# syncbox.net
KiCad netlist of a schematic drawn in EAGLE
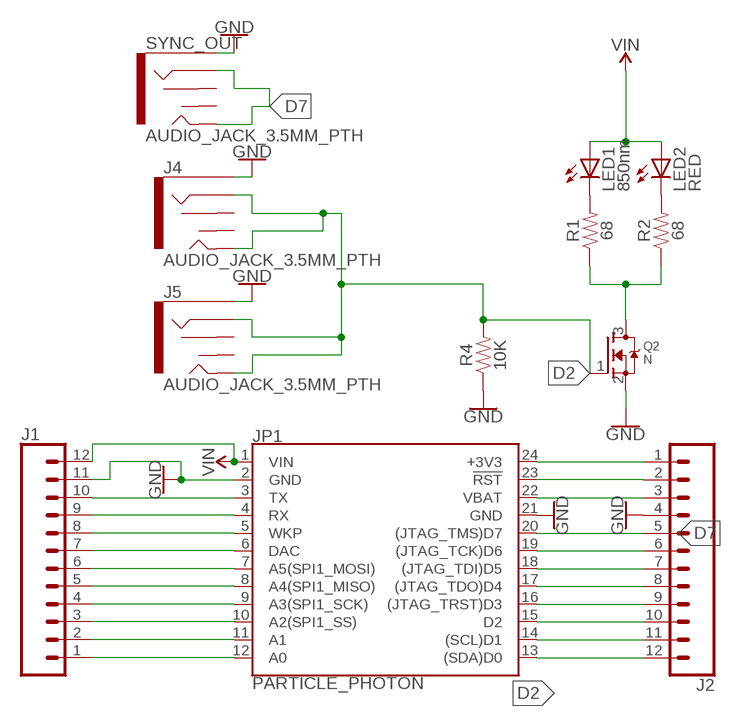
[diagram p0: schematic, sheet 1]

(export (version "E")
  (design (tool "Eeschema 10.0.6"))
  (components
    (comp (ref "J1")
      (value "CONN_12")
      (footprint "eagle-import:1X12")
      (libsource (lib "eagle-import") (part "CONN_12"))
    )
    (comp (ref "J2")
      (value "CONN_12")
      (footprint "eagle-import:1X12")
      (libsource (lib "eagle-import") (part "CONN_12"))
    )
    (comp (ref "J4")
      (value "AUDIO_JACK_3.5MM_PTH")
      (footprint "eagle-import:AUDIO-JACK")
      (libsource (lib "eagle-import") (part "AUDIO_JACK_3.5MM_PTH"))
    )
    (comp (ref "J5")
      (value "AUDIO_JACK_3.5MM_PTH")
      (footprint "eagle-import:AUDIO-JACK")
      (libsource (lib "eagle-import") (part "AUDIO_JACK_3.5MM_PTH"))
    )
    (comp (ref "JP1")
      (value "PARTICLE_PHOTON")
      (footprint "eagle-import:PARTICLE_PHOTON")
      (libsource (lib "eagle-import") (part "PARTICLE_PHOTON"))
    )
    (comp (ref "LED1")
      (value "850nm")
      (footprint "eagle-import:LED5MM")
      (libsource (lib "eagle-import") (part "LED5MM"))
    )
    (comp (ref "LED2")
      (value "RED")
      (footprint "eagle-import:LED5MM")
      (libsource (lib "eagle-import") (part "LED5MM"))
    )
    (comp (ref "Q2")
      (value "N")
      (footprint "eagle-import:SOT23-W")
      (libsource (lib "eagle-import") (part "MOSFET-NWAVE"))
    )
    (comp (ref "R1")
      (value "68")
      (footprint "eagle-import:AXIAL-0.3")
      (libsource (lib "eagle-import") (part "RESISTORAXIAL-0.3"))
    )
    (comp (ref "R2")
      (value "68")
      (footprint "eagle-import:AXIAL-0.3")
      (libsource (lib "eagle-import") (part "RESISTORAXIAL-0.3"))
    )
    (comp (ref "R4")
      (value "10K")
      (footprint "eagle-import:AXIAL-0.3")
      (libsource (lib "eagle-import") (part "RESISTORAXIAL-0.3"))
    )
    (comp (ref "SYNC_OUT")
      (value "AUDIO_JACK_3.5MM_PTH")
      (footprint "eagle-import:AUDIO-JACK")
      (libsource (lib "eagle-import") (part "AUDIO_JACK_3.5MM_PTH"))
    )
  )
  (nets
    (net (code "1") (name "D2") (class "Default")
      (node (ref "J2") (pin "10") (pinfunction "10_10") (pintype "passive"))
      (node (ref "J4") (pin "RING") (pinfunction "RING_RING") (pintype "bidirectional"))
      (node (ref "J4") (pin "TIP") (pinfunction "TIP_TIP") (pintype "bidirectional"))
      (node (ref "J5") (pin "RING") (pinfunction "RING_RING") (pintype "bidirectional"))
      (node (ref "J5") (pin "TIP") (pinfunction "TIP_TIP") (pintype "bidirectional"))
      (node (ref "JP1") (pin "15") (pinfunction "D2_15") (pintype "bidirectional"))
      (node (ref "Q2") (pin "1") (pinfunction "G_1") (pintype "bidirectional"))
      (node (ref "R4") (pin "P$2") (pinfunction "2_P$2") (pintype "passive"))
    )
    (net (code "2") (name "D7") (class "Default")
      (node (ref "J2") (pin "5") (pinfunction "5_5") (pintype "passive"))
      (node (ref "JP1") (pin "20") (pinfunction "(JTAG_TMS)D7_20") (pintype "bidirectional"))
      (node (ref "SYNC_OUT") (pin "RING") (pinfunction "RING_RING") (pintype "bidirectional"))
      (node (ref "SYNC_OUT") (pin "TIP") (pinfunction "TIP_TIP") (pintype "bidirectional"))
    )
    (net (code "3") (name "GND") (class "Default")
      (node (ref "J1") (pin "11") (pinfunction "11_11") (pintype "passive"))
      (node (ref "J2") (pin "4") (pinfunction "4_4") (pintype "passive"))
      (node (ref "J4") (pin "SLEEVE") (pinfunction "SLEEVE_SLEEVE") (pintype "bidirectional"))
      (node (ref "J5") (pin "SLEEVE") (pinfunction "SLEEVE_SLEEVE") (pintype "bidirectional"))
      (node (ref "JP1") (pin "2") (pinfunction "GND_2") (pintype "power_in"))
      (node (ref "JP1") (pin "21") (pinfunction "GND_21") (pintype "power_in"))
      (node (ref "Q2") (pin "2") (pinfunction "S_2") (pintype "bidirectional"))
      (node (ref "R4") (pin "P$1") (pinfunction "1_P$1") (pintype "passive"))
      (node (ref "SYNC_OUT") (pin "SLEEVE") (pinfunction "SLEEVE_SLEEVE") (pintype "bidirectional"))
    )
    (net (code "4") (name "Net-(JP1-(JTAG_TCK)D6)") (class "Default")
      (node (ref "J2") (pin "6") (pinfunction "6_6") (pintype "passive"))
      (node (ref "JP1") (pin "19") (pinfunction "(JTAG_TCK)D6_19") (pintype "bidirectional"))
    )
    (net (code "5") (name "Net-(JP1-(JTAG_TDI)D5)") (class "Default")
      (node (ref "J2") (pin "7") (pinfunction "7_7") (pintype "passive"))
      (node (ref "JP1") (pin "18") (pinfunction "(JTAG_TDI)D5_18") (pintype "bidirectional"))
    )
    (net (code "6") (name "Net-(JP1-(JTAG_TDO)D4)") (class "Default")
      (node (ref "J2") (pin "8") (pinfunction "8_8") (pintype "passive"))
      (node (ref "JP1") (pin "17") (pinfunction "(JTAG_TDO)D4_17") (pintype "bidirectional"))
    )
    (net (code "7") (name "Net-(JP1-(JTAG_TRST)D3)") (class "Default")
      (node (ref "J2") (pin "9") (pinfunction "9_9") (pintype "passive"))
      (node (ref "JP1") (pin "16") (pinfunction "(JTAG_TRST)D3_16") (pintype "bidirectional"))
    )
    (net (code "8") (name "Net-(JP1-(SCL)D1)") (class "Default")
      (node (ref "J2") (pin "11") (pinfunction "11_11") (pintype "passive"))
      (node (ref "JP1") (pin "14") (pinfunction "(SCL)D1_14") (pintype "bidirectional"))
    )
    (net (code "9") (name "Net-(JP1-(SDA)D0)") (class "Default")
      (node (ref "J2") (pin "12") (pinfunction "12_12") (pintype "passive"))
      (node (ref "JP1") (pin "13") (pinfunction "(SDA)D0_13") (pintype "bidirectional"))
    )
    (net (code "10") (name "Net-(JP1-+3V3)") (class "Default")
      (node (ref "J2") (pin "1") (pinfunction "1_1") (pintype "passive"))
      (node (ref "JP1") (pin "24") (pinfunction "+3V3_24") (pintype "power_in"))
    )
    (net (code "11") (name "Net-(JP1-A0)") (class "Default")
      (node (ref "J1") (pin "1") (pinfunction "1_1") (pintype "passive"))
      (node (ref "JP1") (pin "12") (pinfunction "A0_12") (pintype "bidirectional"))
    )
    (net (code "12") (name "Net-(JP1-A1)") (class "Default")
      (node (ref "J1") (pin "2") (pinfunction "2_2") (pintype "passive"))
      (node (ref "JP1") (pin "11") (pinfunction "A1_11") (pintype "bidirectional"))
    )
    (net (code "13") (name "Net-(JP1-A2(SPI1_SS))") (class "Default")
      (node (ref "J1") (pin "3") (pinfunction "3_3") (pintype "passive"))
      (node (ref "JP1") (pin "10") (pinfunction "A2(SPI1_SS)_10") (pintype "bidirectional"))
    )
    (net (code "14") (name "Net-(JP1-A3(SPI1_SCK))") (class "Default")
      (node (ref "J1") (pin "4") (pinfunction "4_4") (pintype "passive"))
      (node (ref "JP1") (pin "9") (pinfunction "A3(SPI1_SCK)_9") (pintype "bidirectional"))
    )
    (net (code "15") (name "Net-(JP1-A4(SPI1_MISO))") (class "Default")
      (node (ref "J1") (pin "5") (pinfunction "5_5") (pintype "passive"))
      (node (ref "JP1") (pin "8") (pinfunction "A4(SPI1_MISO)_8") (pintype "bidirectional"))
    )
    (net (code "16") (name "Net-(JP1-A5(SPI1_MOSI))") (class "Default")
      (node (ref "J1") (pin "6") (pinfunction "6_6") (pintype "passive"))
      (node (ref "JP1") (pin "7") (pinfunction "A5(SPI1_MOSI)_7") (pintype "bidirectional"))
    )
    (net (code "17") (name "Net-(JP1-DAC)") (class "Default")
      (node (ref "J1") (pin "7") (pinfunction "7_7") (pintype "passive"))
      (node (ref "JP1") (pin "6") (pinfunction "DAC_6") (pintype "bidirectional"))
    )
    (net (code "18") (name "Net-(JP1-RX)") (class "Default")
      (node (ref "J1") (pin "9") (pinfunction "9_9") (pintype "passive"))
      (node (ref "JP1") (pin "4") (pinfunction "RX_4") (pintype "bidirectional"))
    )
    (net (code "19") (name "Net-(JP1-TX)") (class "Default")
      (node (ref "J1") (pin "10") (pinfunction "10_10") (pintype "passive"))
      (node (ref "JP1") (pin "3") (pinfunction "TX_3") (pintype "bidirectional"))
    )
    (net (code "20") (name "Net-(JP1-VBAT)") (class "Default")
      (node (ref "J2") (pin "3") (pinfunction "3_3") (pintype "passive"))
      (node (ref "JP1") (pin "22") (pinfunction "VBAT_22") (pintype "power_in"))
    )
    (net (code "21") (name "Net-(JP1-WKP)") (class "Default")
      (node (ref "J1") (pin "8") (pinfunction "8_8") (pintype "passive"))
      (node (ref "JP1") (pin "5") (pinfunction "WKP_5") (pintype "bidirectional"))
    )
    (net (code "22") (name "Net-(JP1-~{RST})") (class "Default")
      (node (ref "J2") (pin "2") (pinfunction "2_2") (pintype "passive"))
      (node (ref "JP1") (pin "23") (pinfunction "~{RST}_23") (pintype "bidirectional"))
    )
    (net (code "23") (name "Net-(LED1-C)") (class "Default")
      (node (ref "LED1") (pin "K") (pinfunction "C_K") (pintype "passive"))
      (node (ref "R1") (pin "P$2") (pinfunction "2_P$2") (pintype "passive"))
    )
    (net (code "24") (name "Net-(LED2-C)") (class "Default")
      (node (ref "LED2") (pin "K") (pinfunction "C_K") (pintype "passive"))
      (node (ref "R2") (pin "P$2") (pinfunction "2_P$2") (pintype "passive"))
    )
    (net (code "25") (name "Net-(Q2-D)") (class "Default")
      (node (ref "Q2") (pin "3") (pinfunction "D_3") (pintype "bidirectional"))
      (node (ref "R1") (pin "P$1") (pinfunction "1_P$1") (pintype "passive"))
      (node (ref "R2") (pin "P$1") (pinfunction "1_P$1") (pintype "passive"))
    )
    (net (code "26") (name "VIN") (class "Default")
      (node (ref "J1") (pin "12") (pinfunction "12_12") (pintype "passive"))
      (node (ref "JP1") (pin "1") (pinfunction "VIN_1") (pintype "power_in"))
      (node (ref "LED1") (pin "A") (pinfunction "A_A") (pintype "passive"))
      (node (ref "LED2") (pin "A") (pinfunction "A_A") (pintype "passive"))
    )
    (net (code "27") (name "unconnected-(J4-PadRSH)") (class "Default")
      (node (ref "J4") (pin "RSH") (pinfunction "RSH_RSH") (pintype "bidirectional"))
    )
    (net (code "28") (name "unconnected-(J4-PadTSH)") (class "Default")
      (node (ref "J4") (pin "TSH") (pinfunction "TSH_TSH") (pintype "bidirectional"))
    )
    (net (code "29") (name "unconnected-(J5-PadRSH)") (class "Default")
      (node (ref "J5") (pin "RSH") (pinfunction "RSH_RSH") (pintype "bidirectional"))
    )
    (net (code "30") (name "unconnected-(J5-PadTSH)") (class "Default")
      (node (ref "J5") (pin "TSH") (pinfunction "TSH_TSH") (pintype "bidirectional"))
    )
    (net (code "31") (name "unconnected-(SYNC_OUT-PadRSH)") (class "Default")
      (node (ref "SYNC_OUT") (pin "RSH") (pinfunction "RSH_RSH") (pintype "bidirectional"))
    )
    (net (code "32") (name "unconnected-(SYNC_OUT-PadTSH)") (class "Default")
      (node (ref "SYNC_OUT") (pin "TSH") (pinfunction "TSH_TSH") (pintype "bidirectional"))
    )
  )
)
